# Temperaturmessung_NTC.net
KiCad netlist of a schematic drawn in EAGLE
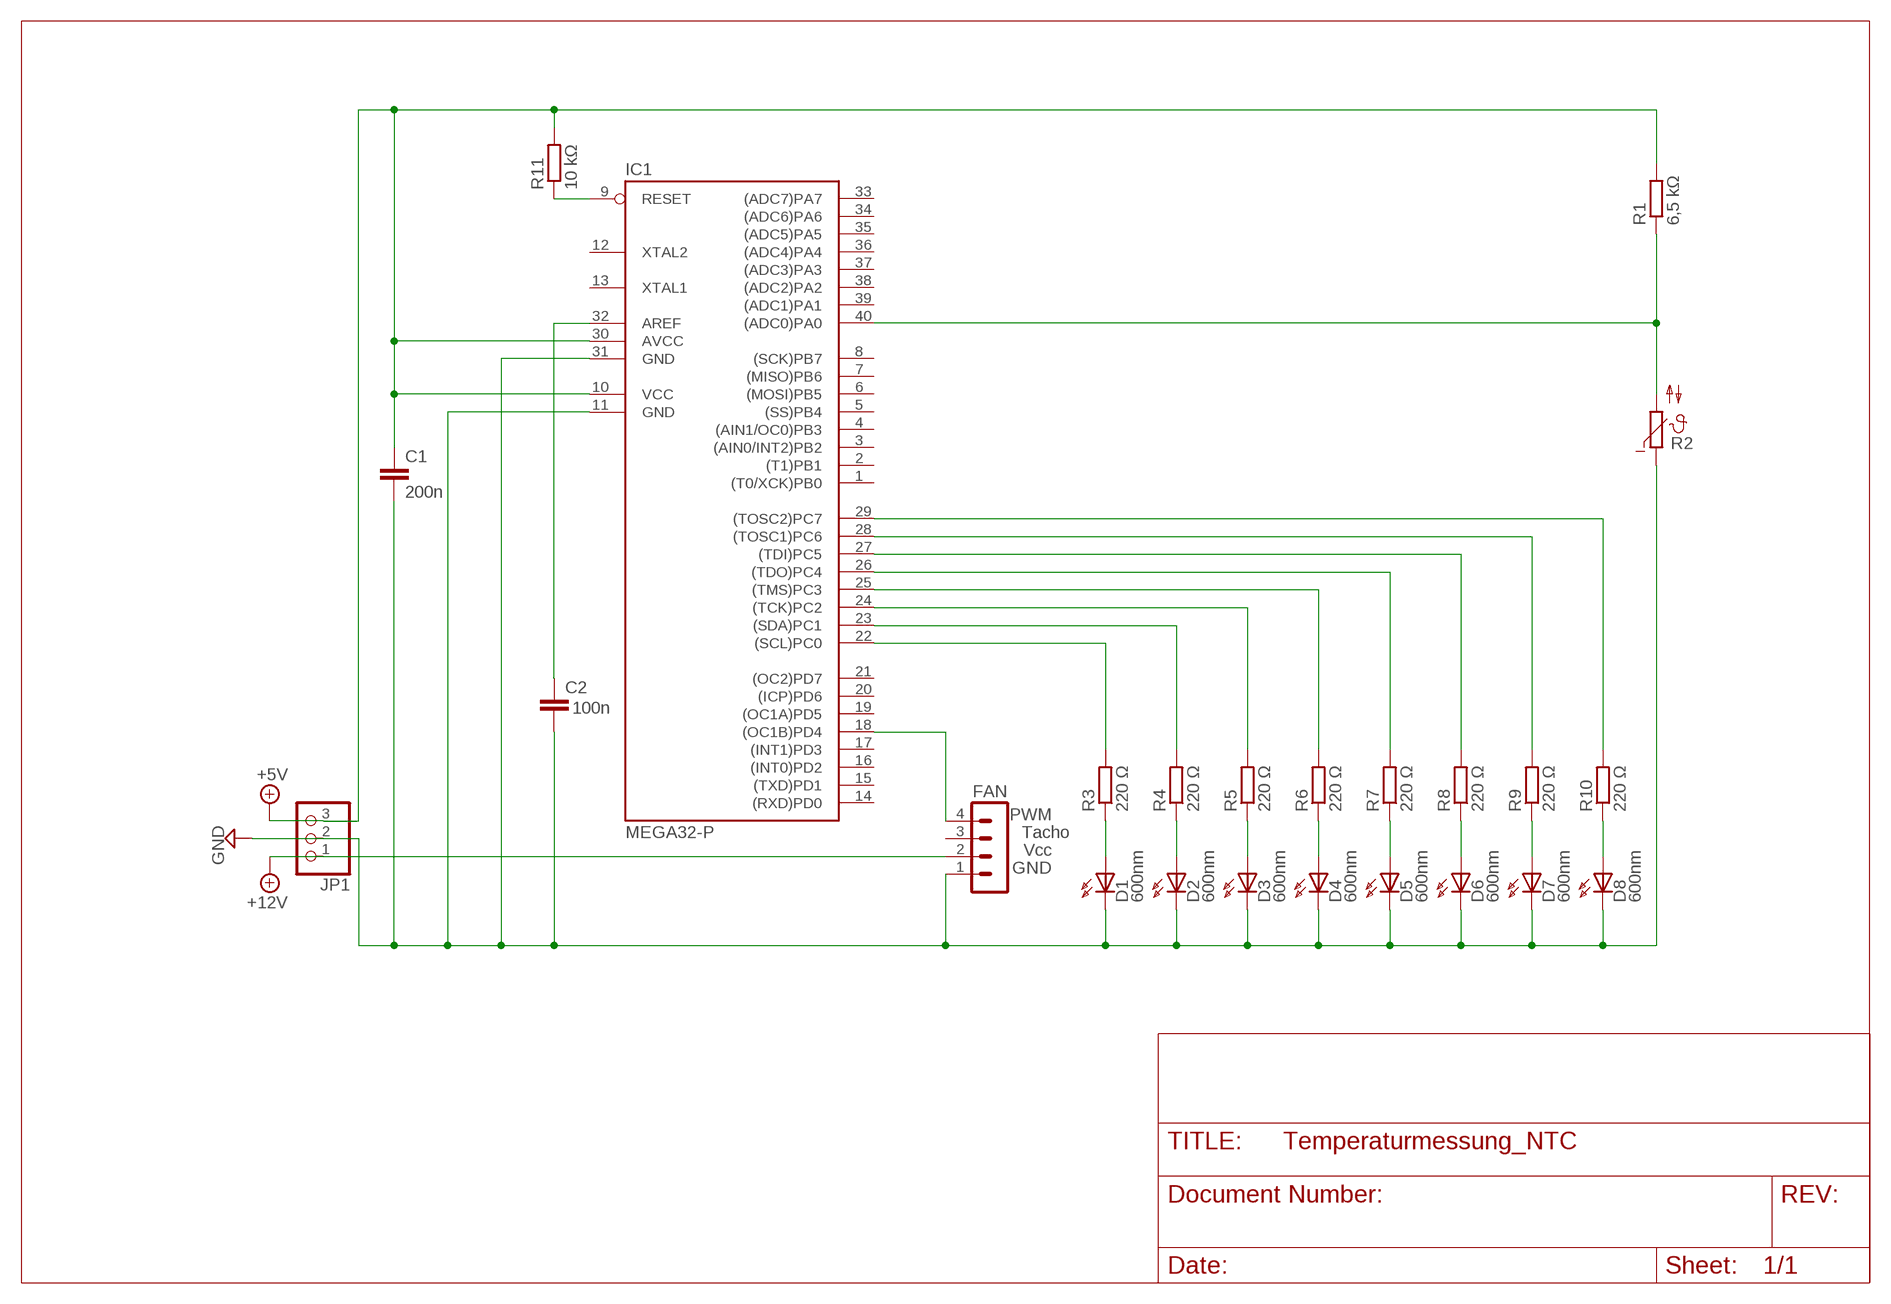
[diagram p0: schematic, sheet 1]

(export (version "E")
  (design (tool "Eeschema 10.0.6"))
  (components
    (comp (ref "C1")
      (value "200n")
      (footprint "eagle-import:C2.5-2")
      (libsource (lib "eagle-import") (part "C2.5/2"))
    )
    (comp (ref "C2")
      (value "C2.5/2")
      (footprint "eagle-import:C2.5-2")
      (fields (field (name "CAP") "100n"))
      (libsource (lib "eagle-import") (part "C2.5/2"))
    )
    (comp (ref "D1")
      (value "600nm")
      (footprint "eagle-import:HLMP6")
      (fields (field (name "MF") "AGILENT TECHNOLOGIES") (field (name "MPN") "HLMP-6500"))
      (libsource (lib "eagle-import") (part "HLMP6"))
    )
    (comp (ref "D2")
      (value "600nm")
      (footprint "eagle-import:HLMP6")
      (fields (field (name "MF") "AGILENT TECHNOLOGIES") (field (name "MPN") "HLMP-6500"))
      (libsource (lib "eagle-import") (part "HLMP6"))
    )
    (comp (ref "D3")
      (value "600nm")
      (footprint "eagle-import:HLMP6")
      (fields (field (name "MF") "AGILENT TECHNOLOGIES") (field (name "MPN") "HLMP-6500"))
      (libsource (lib "eagle-import") (part "HLMP6"))
    )
    (comp (ref "D4")
      (value "600nm")
      (footprint "eagle-import:HLMP6")
      (fields (field (name "MF") "AGILENT TECHNOLOGIES") (field (name "MPN") "HLMP-6500"))
      (libsource (lib "eagle-import") (part "HLMP6"))
    )
    (comp (ref "D5")
      (value "600nm")
      (footprint "eagle-import:HLMP6")
      (fields (field (name "MF") "AGILENT TECHNOLOGIES") (field (name "MPN") "HLMP-6500"))
      (libsource (lib "eagle-import") (part "HLMP6"))
    )
    (comp (ref "D6")
      (value "600nm")
      (footprint "eagle-import:HLMP6")
      (fields (field (name "MF") "AGILENT TECHNOLOGIES") (field (name "MPN") "HLMP-6500"))
      (libsource (lib "eagle-import") (part "HLMP6"))
    )
    (comp (ref "D7")
      (value "600nm")
      (footprint "eagle-import:HLMP6")
      (fields (field (name "MF") "AGILENT TECHNOLOGIES") (field (name "MPN") "HLMP-6500"))
      (libsource (lib "eagle-import") (part "HLMP6"))
    )
    (comp (ref "D8")
      (value "600nm")
      (footprint "eagle-import:HLMP6")
      (fields (field (name "MF") "AGILENT TECHNOLOGIES") (field (name "MPN") "HLMP-6500"))
      (libsource (lib "eagle-import") (part "HLMP6"))
    )
    (comp (ref "FAN")
      (value "MA04-1")
      (footprint "eagle-import:MA04-1")
      (fields
        (field (name "OC_FARNELL") "unknown")
        (field (name "OC_NEWARK") "unknown")
        (field (name "MF") "PWM")
        (field (name "MPN") "Tacho")
        (field (name "OC_FARNELL_1") "Vcc")
        (field (name "OC_NEWARK_1") "GND")
      )
      (libsource (lib "eagle-import") (part "MA04-1"))
    )
    (comp (ref "IC1")
      (value "MEGA32-P")
      (footprint "eagle-import:DIL40")
      (fields (field (name "MPN") "ATMEGA32-16PU"))
      (libsource (lib "eagle-import") (part "MEGA32-P"))
    )
    (comp (ref "JP1")
      (value "PINHD-1X3/90")
      (footprint "eagle-import:1X03_90")
      (libsource (lib "eagle-import") (part "PINHD-1X3/90"))
    )
    (comp (ref "R1")
      (value "6,5 kΩ")
      (footprint "eagle-import:0309_12")
      (libsource (lib "eagle-import") (part "resistor_R-EU_0309/12"))
    )
    (comp (ref "R2")
      (value "NTC644A")
      (footprint "eagle-import:N644A")
      (libsource (lib "eagle-import") (part "NTC644A"))
    )
    (comp (ref "R3")
      (value "220 Ω")
      (footprint "eagle-import:0309_12")
      (libsource (lib "eagle-import") (part "resistor_R-EU_0309/12"))
    )
    (comp (ref "R4")
      (value "220 Ω")
      (footprint "eagle-import:0309_12")
      (libsource (lib "eagle-import") (part "resistor_R-EU_0309/12"))
    )
    (comp (ref "R5")
      (value "220 Ω")
      (footprint "eagle-import:0309_12")
      (libsource (lib "eagle-import") (part "resistor_R-EU_0309/12"))
    )
    (comp (ref "R6")
      (value "220 Ω")
      (footprint "eagle-import:0309_12")
      (libsource (lib "eagle-import") (part "resistor_R-EU_0309/12"))
    )
    (comp (ref "R7")
      (value "220 Ω")
      (footprint "eagle-import:0309_12")
      (libsource (lib "eagle-import") (part "resistor_R-EU_0309/12"))
    )
    (comp (ref "R8")
      (value "220 Ω")
      (footprint "eagle-import:0309_12")
      (libsource (lib "eagle-import") (part "resistor_R-EU_0309/12"))
    )
    (comp (ref "R9")
      (value "220 Ω")
      (footprint "eagle-import:0309_12")
      (libsource (lib "eagle-import") (part "resistor_R-EU_0309/12"))
    )
    (comp (ref "R10")
      (value "220 Ω")
      (footprint "eagle-import:0309_12")
      (libsource (lib "eagle-import") (part "resistor_R-EU_0309/12"))
    )
    (comp (ref "R11")
      (value "10 kΩ")
      (footprint "eagle-import:0309_12")
      (libsource (lib "eagle-import") (part "R-EU_0309/12"))
    )
  )
  (nets
    (net (code "1") (name "+5V") (class "Default")
      (node (ref "C1") (pin "1") (pinfunction "1_1") (pintype "passive"))
      (node (ref "IC1") (pin "10") (pinfunction "VCC_10") (pintype "power_in"))
      (node (ref "IC1") (pin "30") (pinfunction "AVCC_30") (pintype "power_in"))
      (node (ref "JP1") (pin "3") (pinfunction "3_3") (pintype "passive"))
      (node (ref "R1") (pin "2") (pinfunction "2_2") (pintype "passive"))
      (node (ref "R11") (pin "2") (pinfunction "2_2") (pintype "passive"))
    )
    (net (code "2") (name "+12V") (class "Default")
      (node (ref "FAN") (pin "2") (pinfunction "2_2") (pintype "passive"))
      (node (ref "JP1") (pin "1") (pinfunction "1_1") (pintype "passive"))
    )
    (net (code "3") (name "GND") (class "Default")
      (node (ref "C1") (pin "2") (pinfunction "2_2") (pintype "passive"))
      (node (ref "C2") (pin "2") (pinfunction "2_2") (pintype "passive"))
      (node (ref "D1") (pin "K") (pinfunction "K_K") (pintype "passive"))
      (node (ref "D2") (pin "K") (pinfunction "K_K") (pintype "passive"))
      (node (ref "D3") (pin "K") (pinfunction "K_K") (pintype "passive"))
      (node (ref "D4") (pin "K") (pinfunction "K_K") (pintype "passive"))
      (node (ref "D5") (pin "K") (pinfunction "K_K") (pintype "passive"))
      (node (ref "D6") (pin "K") (pinfunction "K_K") (pintype "passive"))
      (node (ref "D7") (pin "K") (pinfunction "K_K") (pintype "passive"))
      (node (ref "D8") (pin "K") (pinfunction "K_K") (pintype "passive"))
      (node (ref "FAN") (pin "1") (pinfunction "1_1") (pintype "passive"))
      (node (ref "IC1") (pin "11") (pinfunction "GND_11") (pintype "power_in"))
      (node (ref "IC1") (pin "31") (pinfunction "GND_31") (pintype "power_in"))
      (node (ref "JP1") (pin "2") (pinfunction "2_2") (pintype "passive"))
      (node (ref "R2") (pin "1") (pinfunction "1_1") (pintype "passive"))
    )
    (net (code "4") (name "Net-(D1-PadA)") (class "Default")
      (node (ref "D1") (pin "A") (pinfunction "A_A") (pintype "passive"))
      (node (ref "R3") (pin "1") (pinfunction "1_1") (pintype "passive"))
    )
    (net (code "5") (name "Net-(D2-PadA)") (class "Default")
      (node (ref "D2") (pin "A") (pinfunction "A_A") (pintype "passive"))
      (node (ref "R4") (pin "1") (pinfunction "1_1") (pintype "passive"))
    )
    (net (code "6") (name "Net-(D3-PadA)") (class "Default")
      (node (ref "D3") (pin "A") (pinfunction "A_A") (pintype "passive"))
      (node (ref "R5") (pin "1") (pinfunction "1_1") (pintype "passive"))
    )
    (net (code "7") (name "Net-(D4-PadA)") (class "Default")
      (node (ref "D4") (pin "A") (pinfunction "A_A") (pintype "passive"))
      (node (ref "R6") (pin "1") (pinfunction "1_1") (pintype "passive"))
    )
    (net (code "8") (name "Net-(D5-PadA)") (class "Default")
      (node (ref "D5") (pin "A") (pinfunction "A_A") (pintype "passive"))
      (node (ref "R7") (pin "1") (pinfunction "1_1") (pintype "passive"))
    )
    (net (code "9") (name "Net-(D6-PadA)") (class "Default")
      (node (ref "D6") (pin "A") (pinfunction "A_A") (pintype "passive"))
      (node (ref "R8") (pin "1") (pinfunction "1_1") (pintype "passive"))
    )
    (net (code "10") (name "Net-(D7-PadA)") (class "Default")
      (node (ref "D7") (pin "A") (pinfunction "A_A") (pintype "passive"))
      (node (ref "R9") (pin "1") (pinfunction "1_1") (pintype "passive"))
    )
    (net (code "11") (name "Net-(D8-PadA)") (class "Default")
      (node (ref "D8") (pin "A") (pinfunction "A_A") (pintype "passive"))
      (node (ref "R10") (pin "1") (pinfunction "1_1") (pintype "passive"))
    )
    (net (code "12") (name "Net-(IC1-(ADC0)PA0)") (class "Default")
      (node (ref "IC1") (pin "40") (pinfunction "(ADC0)PA0_40") (pintype "bidirectional"))
      (node (ref "R1") (pin "1") (pinfunction "1_1") (pintype "passive"))
      (node (ref "R2") (pin "2") (pinfunction "2_2") (pintype "passive"))
    )
    (net (code "13") (name "Net-(IC1-(OC1B)PD4)") (class "Default")
      (node (ref "FAN") (pin "4") (pinfunction "4_4") (pintype "passive"))
      (node (ref "IC1") (pin "18") (pinfunction "(OC1B)PD4_18") (pintype "bidirectional"))
    )
    (net (code "14") (name "Net-(IC1-(SCL)PC0)") (class "Default")
      (node (ref "IC1") (pin "22") (pinfunction "(SCL)PC0_22") (pintype "bidirectional"))
      (node (ref "R3") (pin "2") (pinfunction "2_2") (pintype "passive"))
    )
    (net (code "15") (name "Net-(IC1-(SDA)PC1)") (class "Default")
      (node (ref "IC1") (pin "23") (pinfunction "(SDA)PC1_23") (pintype "bidirectional"))
      (node (ref "R4") (pin "2") (pinfunction "2_2") (pintype "passive"))
    )
    (net (code "16") (name "Net-(IC1-(TCK)PC2)") (class "Default")
      (node (ref "IC1") (pin "24") (pinfunction "(TCK)PC2_24") (pintype "bidirectional"))
      (node (ref "R5") (pin "2") (pinfunction "2_2") (pintype "passive"))
    )
    (net (code "17") (name "Net-(IC1-(TDI)PC5)") (class "Default")
      (node (ref "IC1") (pin "27") (pinfunction "(TDI)PC5_27") (pintype "bidirectional"))
      (node (ref "R8") (pin "2") (pinfunction "2_2") (pintype "passive"))
    )
    (net (code "18") (name "Net-(IC1-(TDO)PC4)") (class "Default")
      (node (ref "IC1") (pin "26") (pinfunction "(TDO)PC4_26") (pintype "bidirectional"))
      (node (ref "R7") (pin "2") (pinfunction "2_2") (pintype "passive"))
    )
    (net (code "19") (name "Net-(IC1-(TMS)PC3)") (class "Default")
      (node (ref "IC1") (pin "25") (pinfunction "(TMS)PC3_25") (pintype "bidirectional"))
      (node (ref "R6") (pin "2") (pinfunction "2_2") (pintype "passive"))
    )
    (net (code "20") (name "Net-(IC1-(TOSC1)PC6)") (class "Default")
      (node (ref "IC1") (pin "28") (pinfunction "(TOSC1)PC6_28") (pintype "bidirectional"))
      (node (ref "R9") (pin "2") (pinfunction "2_2") (pintype "passive"))
    )
    (net (code "21") (name "Net-(IC1-(TOSC2)PC7)") (class "Default")
      (node (ref "IC1") (pin "29") (pinfunction "(TOSC2)PC7_29") (pintype "bidirectional"))
      (node (ref "R10") (pin "2") (pinfunction "2_2") (pintype "passive"))
    )
    (net (code "22") (name "Net-(IC1-AREF)") (class "Default")
      (node (ref "C2") (pin "1") (pinfunction "1_1") (pintype "passive"))
      (node (ref "IC1") (pin "32") (pinfunction "AREF_32") (pintype "passive"))
    )
    (net (code "23") (name "Net-(IC1-RESET)") (class "Default")
      (node (ref "IC1") (pin "9") (pinfunction "RESET_9") (pintype "input"))
      (node (ref "R11") (pin "1") (pinfunction "1_1") (pintype "passive"))
    )
    (net (code "24") (name "unconnected-(FAN-Pad3)") (class "Default")
      (node (ref "FAN") (pin "3") (pinfunction "3_3") (pintype "passive"))
    )
    (net (code "25") (name "unconnected-(IC1-(ADC1)PA1-Pad39)") (class "Default")
      (node (ref "IC1") (pin "39") (pinfunction "(ADC1)PA1_39") (pintype "bidirectional"))
    )
    (net (code "26") (name "unconnected-(IC1-(ADC2)PA2-Pad38)") (class "Default")
      (node (ref "IC1") (pin "38") (pinfunction "(ADC2)PA2_38") (pintype "bidirectional"))
    )
    (net (code "27") (name "unconnected-(IC1-(ADC3)PA3-Pad37)") (class "Default")
      (node (ref "IC1") (pin "37") (pinfunction "(ADC3)PA3_37") (pintype "bidirectional"))
    )
    (net (code "28") (name "unconnected-(IC1-(ADC4)PA4-Pad36)") (class "Default")
      (node (ref "IC1") (pin "36") (pinfunction "(ADC4)PA4_36") (pintype "bidirectional"))
    )
    (net (code "29") (name "unconnected-(IC1-(ADC5)PA5-Pad35)") (class "Default")
      (node (ref "IC1") (pin "35") (pinfunction "(ADC5)PA5_35") (pintype "bidirectional"))
    )
    (net (code "30") (name "unconnected-(IC1-(ADC6)PA6-Pad34)") (class "Default")
      (node (ref "IC1") (pin "34") (pinfunction "(ADC6)PA6_34") (pintype "bidirectional"))
    )
    (net (code "31") (name "unconnected-(IC1-(ADC7)PA7-Pad33)") (class "Default")
      (node (ref "IC1") (pin "33") (pinfunction "(ADC7)PA7_33") (pintype "bidirectional"))
    )
    (net (code "32") (name "unconnected-(IC1-(AIN0{slash}INT2)PB2-Pad3)") (class "Default")
      (node (ref "IC1") (pin "3") (pinfunction "(AIN0/INT2)PB2_3") (pintype "bidirectional"))
    )
    (net (code "33") (name "unconnected-(IC1-(AIN1{slash}OC0)PB3-Pad4)") (class "Default")
      (node (ref "IC1") (pin "4") (pinfunction "(AIN1/OC0)PB3_4") (pintype "bidirectional"))
    )
    (net (code "34") (name "unconnected-(IC1-(ICP)PD6-Pad20)") (class "Default")
      (node (ref "IC1") (pin "20") (pinfunction "(ICP)PD6_20") (pintype "bidirectional"))
    )
    (net (code "35") (name "unconnected-(IC1-(INT0)PD2-Pad16)") (class "Default")
      (node (ref "IC1") (pin "16") (pinfunction "(INT0)PD2_16") (pintype "bidirectional"))
    )
    (net (code "36") (name "unconnected-(IC1-(INT1)PD3-Pad17)") (class "Default")
      (node (ref "IC1") (pin "17") (pinfunction "(INT1)PD3_17") (pintype "bidirectional"))
    )
    (net (code "37") (name "unconnected-(IC1-(MISO)PB6-Pad7)") (class "Default")
      (node (ref "IC1") (pin "7") (pinfunction "(MISO)PB6_7") (pintype "bidirectional"))
    )
    (net (code "38") (name "unconnected-(IC1-(MOSI)PB5-Pad6)") (class "Default")
      (node (ref "IC1") (pin "6") (pinfunction "(MOSI)PB5_6") (pintype "bidirectional"))
    )
    (net (code "39") (name "unconnected-(IC1-(OC1A)PD5-Pad19)") (class "Default")
      (node (ref "IC1") (pin "19") (pinfunction "(OC1A)PD5_19") (pintype "bidirectional"))
    )
    (net (code "40") (name "unconnected-(IC1-(OC2)PD7-Pad21)") (class "Default")
      (node (ref "IC1") (pin "21") (pinfunction "(OC2)PD7_21") (pintype "bidirectional"))
    )
    (net (code "41") (name "unconnected-(IC1-(RXD)PD0-Pad14)") (class "Default")
      (node (ref "IC1") (pin "14") (pinfunction "(RXD)PD0_14") (pintype "bidirectional"))
    )
    (net (code "42") (name "unconnected-(IC1-(SCK)PB7-Pad8)") (class "Default")
      (node (ref "IC1") (pin "8") (pinfunction "(SCK)PB7_8") (pintype "bidirectional"))
    )
    (net (code "43") (name "unconnected-(IC1-(SS)PB4-Pad5)") (class "Default")
      (node (ref "IC1") (pin "5") (pinfunction "(SS)PB4_5") (pintype "bidirectional"))
    )
    (net (code "44") (name "unconnected-(IC1-(T0{slash}XCK)PB0-Pad1)") (class "Default")
      (node (ref "IC1") (pin "1") (pinfunction "(T0/XCK)PB0_1") (pintype "bidirectional"))
    )
    (net (code "45") (name "unconnected-(IC1-(T1)PB1-Pad2)") (class "Default")
      (node (ref "IC1") (pin "2") (pinfunction "(T1)PB1_2") (pintype "bidirectional"))
    )
    (net (code "46") (name "unconnected-(IC1-(TXD)PD1-Pad15)") (class "Default")
      (node (ref "IC1") (pin "15") (pinfunction "(TXD)PD1_15") (pintype "bidirectional"))
    )
    (net (code "47") (name "unconnected-(IC1-XTAL1-Pad13)") (class "Default")
      (node (ref "IC1") (pin "13") (pinfunction "XTAL1_13") (pintype "bidirectional"))
    )
    (net (code "48") (name "unconnected-(IC1-XTAL2-Pad12)") (class "Default")
      (node (ref "IC1") (pin "12") (pinfunction "XTAL2_12") (pintype "bidirectional"))
    )
  )
)
